# plugbrd4.net
KiCad netlist of a schematic drawn in EAGLE
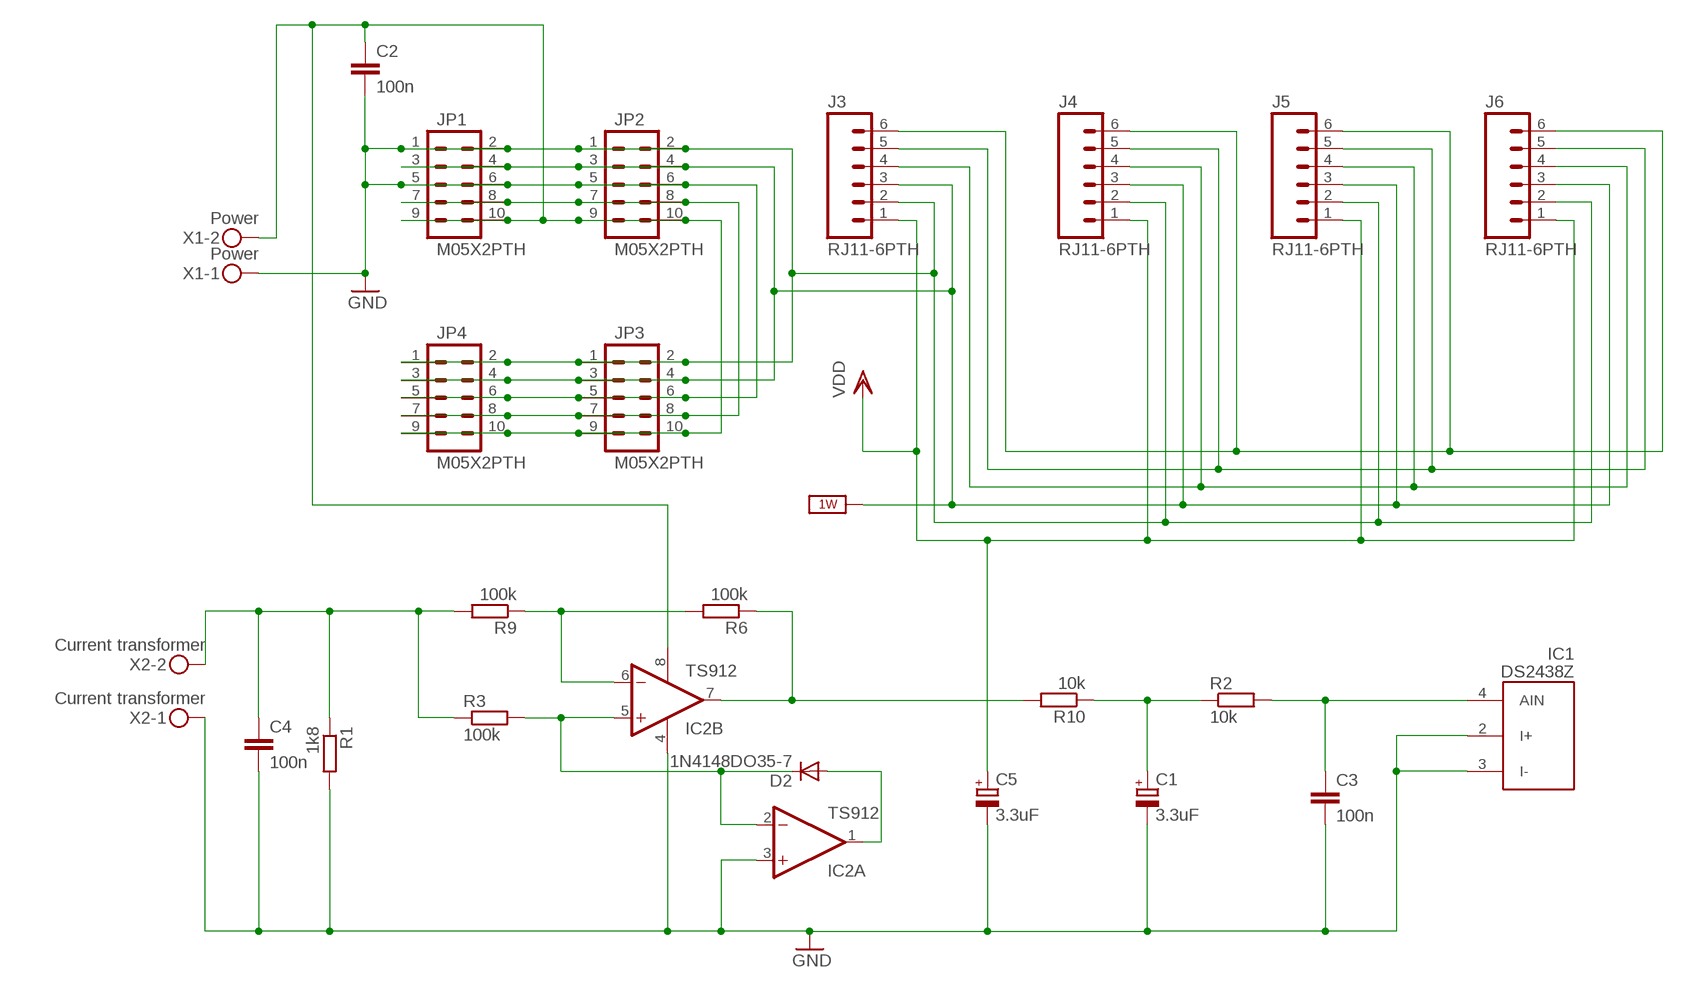
[diagram p0: schematic, sheet 1]

(export (version "E")
  (design (tool "Eeschema 10.0.6"))
  (components
    (comp (ref "C1")
      (value "3.3uF")
      (footprint "eagle-import:E5-6")
      (libsource (lib "eagle-import") (part "CPOL-EUE5-6"))
    )
    (comp (ref "C2")
      (value "100n")
      (footprint "eagle-import:C050-025X075")
      (libsource (lib "eagle-import") (part "C-EU050-025X075"))
    )
    (comp (ref "C3")
      (value "100n")
      (footprint "eagle-import:C050-025X075")
      (libsource (lib "eagle-import") (part "C-EU050-025X075"))
    )
    (comp (ref "C4")
      (value "100n")
      (footprint "eagle-import:C050-025X075")
      (libsource (lib "eagle-import") (part "C-EU050-025X075"))
    )
    (comp (ref "C5")
      (value "3.3uF")
      (footprint "eagle-import:E5-6")
      (libsource (lib "eagle-import") (part "CPOL-EUE5-6"))
    )
    (comp (ref "D2")
      (value "1N4148DO35-7")
      (footprint "eagle-import:DO35-7")
      (libsource (lib "eagle-import") (part "1N4148DO35-7"))
    )
    (comp (ref "IC1")
      (value "DS2438Z")
      (footprint "eagle-import:SO08")
      (libsource (lib "eagle-import") (part "DS2438Z"))
    )
    (comp (ref "IC2")
      (value "TS912")
      (footprint "eagle-import:SO08")
      (libsource (lib "eagle-import") (part "2AMP_P8+4D"))
    )
    (comp (ref "J3")
      (value "RJ11-6PTH")
      (footprint "eagle-import:RJ11-6")
      (libsource (lib "eagle-import") (part "RJ11-6PTH"))
    )
    (comp (ref "J4")
      (value "RJ11-6PTH")
      (footprint "eagle-import:RJ11-6")
      (libsource (lib "eagle-import") (part "RJ11-6PTH"))
    )
    (comp (ref "J5")
      (value "RJ11-6PTH")
      (footprint "eagle-import:RJ11-6")
      (libsource (lib "eagle-import") (part "RJ11-6PTH"))
    )
    (comp (ref "J6")
      (value "RJ11-6PTH")
      (footprint "eagle-import:RJ11-6")
      (libsource (lib "eagle-import") (part "RJ11-6PTH"))
    )
    (comp (ref "JP1")
      (value "M05X2PTH")
      (footprint "eagle-import:AVR_ICSP")
      (libsource (lib "eagle-import") (part "M05X2PTH"))
    )
    (comp (ref "JP2")
      (value "M05X2PTH")
      (footprint "eagle-import:AVR_ICSP")
      (libsource (lib "eagle-import") (part "M05X2PTH"))
    )
    (comp (ref "JP3")
      (value "M05X2PTH")
      (footprint "eagle-import:AVR_ICSP")
      (libsource (lib "eagle-import") (part "M05X2PTH"))
    )
    (comp (ref "JP4")
      (value "M05X2PTH")
      (footprint "eagle-import:AVR_ICSP")
      (libsource (lib "eagle-import") (part "M05X2PTH"))
    )
    (comp (ref "R1")
      (value "1k8")
      (footprint "eagle-import:0207_12")
      (libsource (lib "eagle-import") (part "R-EU_0207/12"))
    )
    (comp (ref "R2")
      (value "10k")
      (footprint "eagle-import:0207_12")
      (libsource (lib "eagle-import") (part "R-EU_0207/12"))
    )
    (comp (ref "R3")
      (value "100k")
      (footprint "eagle-import:0207_12")
      (libsource (lib "eagle-import") (part "R-EU_0207/12"))
    )
    (comp (ref "R6")
      (value "100k")
      (footprint "eagle-import:0207_12")
      (libsource (lib "eagle-import") (part "R-EU_0207/12"))
    )
    (comp (ref "R9")
      (value "100k")
      (footprint "eagle-import:0207_12")
      (libsource (lib "eagle-import") (part "R-EU_0207/12"))
    )
    (comp (ref "R10")
      (value "10k")
      (footprint "eagle-import:0207_12")
      (libsource (lib "eagle-import") (part "R-EU_0207/12"))
    )
    (comp (ref "X1")
      (value "Power")
      (footprint "eagle-import:MKDSN1,5_2-5,08")
      (libsource (lib "eagle-import") (part "MKDSN1,5/2-5,08"))
    )
    (comp (ref "X2")
      (value "Current transformer")
      (footprint "eagle-import:MKDSN1,5_2-5,08")
      (libsource (lib "eagle-import") (part "MKDSN1,5/2-5,08"))
    )
  )
  (nets
    (net (code "1") (name "1W_SUP") (class "Default")
      (node (ref "J3") (pin "3") (pinfunction "3_3") (pintype "passive"))
      (node (ref "J4") (pin "3") (pinfunction "3_3") (pintype "passive"))
      (node (ref "J5") (pin "3") (pinfunction "3_3") (pintype "passive"))
      (node (ref "J6") (pin "3") (pinfunction "3_3") (pintype "passive"))
      (node (ref "JP1") (pin "3") (pinfunction "3_3") (pintype "passive"))
      (node (ref "JP1") (pin "4") (pinfunction "4_4") (pintype "passive"))
      (node (ref "JP2") (pin "3") (pinfunction "3_3") (pintype "passive"))
      (node (ref "JP2") (pin "4") (pinfunction "4_4") (pintype "passive"))
      (node (ref "JP3") (pin "3") (pinfunction "3_3") (pintype "passive"))
      (node (ref "JP3") (pin "4") (pinfunction "4_4") (pintype "passive"))
      (node (ref "JP4") (pin "3") (pinfunction "3_3") (pintype "passive"))
      (node (ref "JP4") (pin "4") (pinfunction "4_4") (pintype "passive"))
    )
    (net (code "2") (name "GND") (class "Default")
      (node (ref "C1") (pin "-") (pinfunction "-_-") (pintype "passive"))
      (node (ref "C2") (pin "2") (pinfunction "2_2") (pintype "passive"))
      (node (ref "C3") (pin "2") (pinfunction "2_2") (pintype "passive"))
      (node (ref "C4") (pin "2") (pinfunction "2_2") (pintype "passive"))
      (node (ref "C5") (pin "-") (pinfunction "-_-") (pintype "passive"))
      (node (ref "IC1") (pin "2") (pinfunction "I+_2") (pintype "input"))
      (node (ref "IC1") (pin "3") (pinfunction "I-_3") (pintype "input"))
      (node (ref "IC2") (pin "3") (pinfunction "+IN_3") (pintype "input"))
      (node (ref "IC2") (pin "4") (pinfunction "V-_4") (pintype "power_in"))
      (node (ref "J3") (pin "2") (pinfunction "2_2") (pintype "passive"))
      (node (ref "J4") (pin "2") (pinfunction "2_2") (pintype "passive"))
      (node (ref "J5") (pin "2") (pinfunction "2_2") (pintype "passive"))
      (node (ref "J6") (pin "2") (pinfunction "2_2") (pintype "passive"))
      (node (ref "JP1") (pin "1") (pinfunction "1_1") (pintype "passive"))
      (node (ref "JP1") (pin "2") (pinfunction "2_2") (pintype "passive"))
      (node (ref "JP1") (pin "5") (pinfunction "5_5") (pintype "passive"))
      (node (ref "JP1") (pin "6") (pinfunction "6_6") (pintype "passive"))
      (node (ref "JP2") (pin "1") (pinfunction "1_1") (pintype "passive"))
      (node (ref "JP2") (pin "2") (pinfunction "2_2") (pintype "passive"))
      (node (ref "JP2") (pin "5") (pinfunction "5_5") (pintype "passive"))
      (node (ref "JP2") (pin "6") (pinfunction "6_6") (pintype "passive"))
      (node (ref "JP3") (pin "1") (pinfunction "1_1") (pintype "passive"))
      (node (ref "JP3") (pin "2") (pinfunction "2_2") (pintype "passive"))
      (node (ref "JP3") (pin "5") (pinfunction "5_5") (pintype "passive"))
      (node (ref "JP3") (pin "6") (pinfunction "6_6") (pintype "passive"))
      (node (ref "JP4") (pin "1") (pinfunction "1_1") (pintype "passive"))
      (node (ref "JP4") (pin "2") (pinfunction "2_2") (pintype "passive"))
      (node (ref "JP4") (pin "5") (pinfunction "5_5") (pintype "passive"))
      (node (ref "JP4") (pin "6") (pinfunction "6_6") (pintype "passive"))
      (node (ref "R1") (pin "2") (pinfunction "2_2") (pintype "passive"))
      (node (ref "X1") (pin "1") (pinfunction "KL_1") (pintype "passive"))
      (node (ref "X2") (pin "1") (pinfunction "KL_1") (pintype "passive"))
    )
    (net (code "3") (name "Net-(C1-Pad+)") (class "Default")
      (node (ref "C1") (pin "+") (pinfunction "+_+") (pintype "passive"))
      (node (ref "R10") (pin "1") (pinfunction "1_1") (pintype "passive"))
      (node (ref "R2") (pin "1") (pinfunction "1_1") (pintype "passive"))
    )
    (net (code "4") (name "Net-(IC1A-AIN)") (class "Default")
      (node (ref "C3") (pin "1") (pinfunction "1_1") (pintype "passive"))
      (node (ref "IC1") (pin "4") (pinfunction "AIN_4") (pintype "input"))
      (node (ref "R2") (pin "2") (pinfunction "2_2") (pintype "passive"))
    )
    (net (code "5") (name "Net-(IC2A--IN)") (class "Default")
      (node (ref "D2") (pin "C") (pinfunction "C_C") (pintype "passive"))
      (node (ref "IC2") (pin "2") (pinfunction "-IN_2") (pintype "input"))
      (node (ref "IC2") (pin "5") (pinfunction "+IN_5") (pintype "input"))
      (node (ref "R3") (pin "2") (pinfunction "2_2") (pintype "passive"))
    )
    (net (code "6") (name "Net-(IC2A-OUT)") (class "Default")
      (node (ref "D2") (pin "A") (pinfunction "A_A") (pintype "passive"))
      (node (ref "IC2") (pin "1") (pinfunction "OUT_1") (pintype "output"))
    )
    (net (code "7") (name "Net-(IC2B--IN)") (class "Default")
      (node (ref "IC2") (pin "6") (pinfunction "-IN_6") (pintype "input"))
      (node (ref "R6") (pin "2") (pinfunction "2_2") (pintype "passive"))
      (node (ref "R9") (pin "1") (pinfunction "1_1") (pintype "passive"))
    )
    (net (code "8") (name "Net-(IC2B-OUT)") (class "Default")
      (node (ref "IC2") (pin "7") (pinfunction "OUT_7") (pintype "output"))
      (node (ref "R10") (pin "2") (pinfunction "2_2") (pintype "passive"))
      (node (ref "R6") (pin "1") (pinfunction "1_1") (pintype "passive"))
    )
    (net (code "9") (name "Net-(IC2C-V+)") (class "Default")
      (node (ref "C2") (pin "1") (pinfunction "1_1") (pintype "passive"))
      (node (ref "IC2") (pin "8") (pinfunction "V+_8") (pintype "power_in"))
      (node (ref "JP1") (pin "10") (pinfunction "10_10") (pintype "passive"))
      (node (ref "JP1") (pin "9") (pinfunction "9_9") (pintype "passive"))
      (node (ref "JP2") (pin "10") (pinfunction "10_10") (pintype "passive"))
      (node (ref "JP2") (pin "9") (pinfunction "9_9") (pintype "passive"))
      (node (ref "JP3") (pin "10") (pinfunction "10_10") (pintype "passive"))
      (node (ref "JP3") (pin "9") (pinfunction "9_9") (pintype "passive"))
      (node (ref "JP4") (pin "10") (pinfunction "10_10") (pintype "passive"))
      (node (ref "JP4") (pin "9") (pinfunction "9_9") (pintype "passive"))
      (node (ref "X1") (pin "2") (pinfunction "KL_2") (pintype "passive"))
    )
    (net (code "10") (name "Net-(J3-Pad4)") (class "Default")
      (node (ref "J3") (pin "4") (pinfunction "4_4") (pintype "passive"))
      (node (ref "J4") (pin "4") (pinfunction "4_4") (pintype "passive"))
      (node (ref "J5") (pin "4") (pinfunction "4_4") (pintype "passive"))
      (node (ref "J6") (pin "4") (pinfunction "4_4") (pintype "passive"))
    )
    (net (code "11") (name "Net-(J3-Pad5)") (class "Default")
      (node (ref "J3") (pin "5") (pinfunction "5_5") (pintype "passive"))
      (node (ref "J4") (pin "5") (pinfunction "5_5") (pintype "passive"))
      (node (ref "J5") (pin "5") (pinfunction "5_5") (pintype "passive"))
      (node (ref "J6") (pin "5") (pinfunction "5_5") (pintype "passive"))
    )
    (net (code "12") (name "Net-(J3-Pad6)") (class "Default")
      (node (ref "J3") (pin "6") (pinfunction "6_6") (pintype "passive"))
      (node (ref "J4") (pin "6") (pinfunction "6_6") (pintype "passive"))
      (node (ref "J5") (pin "6") (pinfunction "6_6") (pintype "passive"))
      (node (ref "J6") (pin "6") (pinfunction "6_6") (pintype "passive"))
    )
    (net (code "13") (name "Net-(JP1-Pad7)") (class "Default")
      (node (ref "JP1") (pin "7") (pinfunction "7_7") (pintype "passive"))
      (node (ref "JP1") (pin "8") (pinfunction "8_8") (pintype "passive"))
      (node (ref "JP2") (pin "7") (pinfunction "7_7") (pintype "passive"))
      (node (ref "JP2") (pin "8") (pinfunction "8_8") (pintype "passive"))
      (node (ref "JP3") (pin "7") (pinfunction "7_7") (pintype "passive"))
      (node (ref "JP3") (pin "8") (pinfunction "8_8") (pintype "passive"))
      (node (ref "JP4") (pin "7") (pinfunction "7_7") (pintype "passive"))
      (node (ref "JP4") (pin "8") (pinfunction "8_8") (pintype "passive"))
    )
    (net (code "14") (name "Net-(X2B-KL)") (class "Default")
      (node (ref "C4") (pin "1") (pinfunction "1_1") (pintype "passive"))
      (node (ref "R1") (pin "1") (pinfunction "1_1") (pintype "passive"))
      (node (ref "R3") (pin "1") (pinfunction "1_1") (pintype "passive"))
      (node (ref "R9") (pin "2") (pinfunction "2_2") (pintype "passive"))
      (node (ref "X2") (pin "2") (pinfunction "KL_2") (pintype "passive"))
    )
    (net (code "15") (name "VDD") (class "Default")
      (node (ref "C5") (pin "+") (pinfunction "+_+") (pintype "passive"))
      (node (ref "J3") (pin "1") (pinfunction "1_1") (pintype "passive"))
      (node (ref "J4") (pin "1") (pinfunction "1_1") (pintype "passive"))
      (node (ref "J5") (pin "1") (pinfunction "1_1") (pintype "passive"))
      (node (ref "J6") (pin "1") (pinfunction "1_1") (pintype "passive"))
    )
  )
)
